# Tramdo.net
KiCad netlist of a schematic drawn in Altium Designer
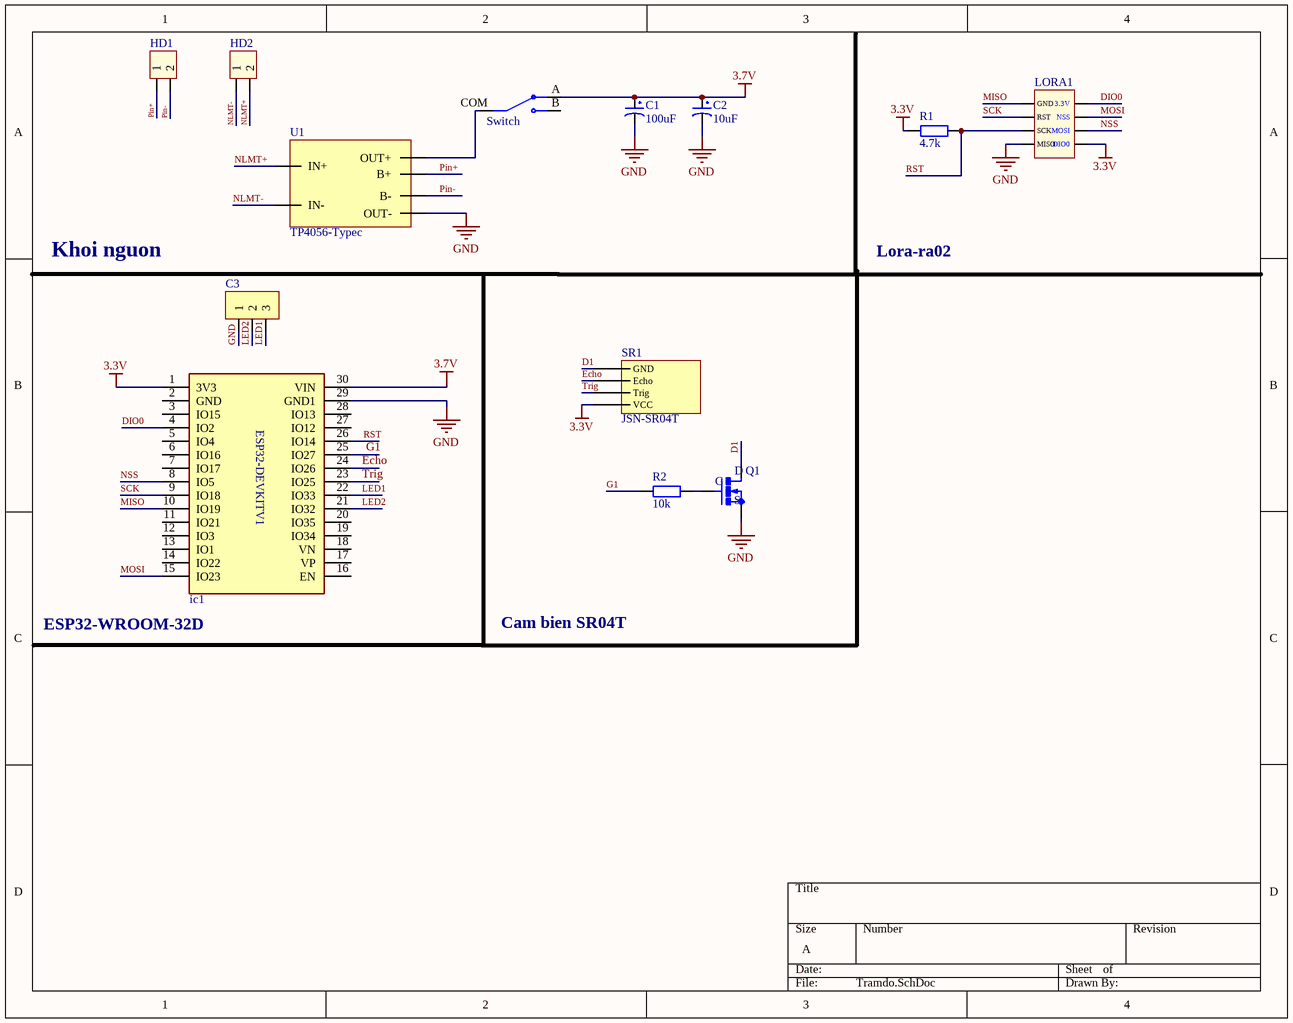
[diagram p0: Tramdo.SchDoc]

(export (version "E")
  (design (tool "Eeschema 10.0.6"))
  (components
    (comp (ref "C1")
      (value "100uF")
      (footprint "tu hoa 5mm")
      (description "Cắm")
      (libsource (lib "Altium_Lib_by_KhueNguyenCreator") (part "Tu Hoa 100uF 16V 5x11"))
    )
    (comp (ref "C2")
      (value "10uF")
      (footprint "tu hoa 4mm")
      (description "Cắm")
      (libsource (lib "Altium_Lib_by_KhueNguyenCreator") (part "Tu Hoa 10uF 16V 4x7"))
    )
    (comp (ref "C3")
      (value "JP3")
      (footprint "JP3-C1T")
      (description "WR-PHD 2.54 mm Angled Socket Header")
      (fields
        (field (name "MANUFACTURER") "Würth Elektronik eiSos GmbH")
        (field (name "PARTNO") "613003143121")
        (field (name "CREATED BY") "Karrer Zheng")
      )
      (libsource (lib "KhanhBK_Library_4") (part "JP3"))
    )
    (comp (ref "HD1")
      (value "Header 2")
      (footprint "HED2")
      (description "Header 2 (Green)")
      (libsource (lib "Integrated_Library1") (part "Hed2"))
    )
    (comp (ref "HD2")
      (value "Header 2")
      (footprint "HED2")
      (description "Header 2 (Green)")
      (libsource (lib "Integrated_Library1") (part "Hed2"))
    )
    (comp (ref "ic1")
      (value "ESP32 DevKit 30Pin")
      (footprint "ESP32 DevKit V1 30Pin CAo")
      (libsource (lib "Integrated_Library1") (part "ESP32 DevKit 30Pin"))
    )
    (comp (ref "LORA1")
      (value "Connector 4x2")
      (footprint "Lora-ra02")
      (libsource (lib "Thuvien_Tramdo") (part "LORA-Ra-02"))
    )
    (comp (ref "Q1")
      (value "2N7000")
      (footprint "TO92")
      (description "N-Channel 60 V 200mA (Ta) 400mW (Ta) Through Hole TO-92-3")
      (fields (field (name "MF") "onsemi"))
      (libsource (lib "Thuvien_Tramdo") (part "2N7000"))
    )
    (comp (ref "R1")
      (value "4.7k")
      (footprint "tro vach 1/4w")
      (description "Cắm")
      (libsource (lib "Altium_Lib_by_KhueNguyenCreator") (part "Tro Vach 1/4W 1% 4.7k"))
    )
    (comp (ref "R2")
      (value "10k")
      (footprint "tro vach 1/4w")
      (description "Cắm")
      (libsource (lib "Altium_Lib_by_KhueNguyenCreator") (part "Tro Vach 1/4W 1% 10k"))
    )
    (comp (ref "S1")
      (value "Switch")
      (footprint "SW_R1966ABLKBLKFR")
      (fields (field (name "MF") "E-Switch") (field (name "MP") "R1966ABLKBLKFR"))
      (libsource (lib "Integrated_Library1") (part "R1966ABLKBLKFR"))
    )
    (comp (ref "SR1")
      (value "JSN-SR04T")
      (footprint "JSN-SR04T")
      (description "Sensor sieu am")
      (libsource (lib "Thuvien_Tramdo") (part "JSN-SR04T"))
    )
    (comp (ref "U1")
      (value "TP4056-Typec")
      (footprint "TP4056")
      (libsource (lib "Thuvien_Tramdo") (part "TP4056-Typec"))
    )
  )
  (nets
    (net (code "1") (name "/D1") (class "Default")
      (node (ref "Q1") (pin "3") (pinfunction "D_3") (pintype "passive"))
      (node (ref "SR1") (pin "GND") (pinfunction "GND_GND") (pintype "passive"))
    )
    (net (code "2") (name "/DIO0") (class "Default")
      (node (ref "LORA1") (pin "5") (pinfunction "3.3V_5") (pintype "passive"))
      (node (ref "ic1") (pin "4") (pinfunction "IO2_4") (pintype "passive"))
    )
    (net (code "3") (name "/Echo") (class "Default")
      (node (ref "SR1") (pin "Echo") (pinfunction "Echo_Echo") (pintype "passive"))
      (node (ref "ic1") (pin "24") (pinfunction "IO26_24") (pintype "passive"))
    )
    (net (code "4") (name "/G1") (class "Default")
      (node (ref "R2") (pin "1") (pinfunction "1_1") (pintype "passive"))
      (node (ref "ic1") (pin "25") (pinfunction "IO27_25") (pintype "passive"))
    )
    (net (code "5") (name "/LED1") (class "Default")
      (node (ref "C3") (pin "3") (pinfunction "3_3") (pintype "passive"))
      (node (ref "ic1") (pin "22") (pinfunction "IO33_22") (pintype "passive"))
    )
    (net (code "6") (name "/LED2") (class "Default")
      (node (ref "C3") (pin "2") (pinfunction "2_2") (pintype "passive"))
      (node (ref "ic1") (pin "21") (pinfunction "IO32_21") (pintype "passive"))
    )
    (net (code "7") (name "/MISO") (class "Default")
      (node (ref "LORA1") (pin "1") (pinfunction "GND_1") (pintype "passive"))
      (node (ref "ic1") (pin "10") (pinfunction "IO19_10") (pintype "passive"))
    )
    (net (code "8") (name "/MOSI") (class "Default")
      (node (ref "LORA1") (pin "6") (pinfunction "NSS_6") (pintype "passive"))
      (node (ref "ic1") (pin "15") (pinfunction "IO23_15") (pintype "passive"))
    )
    (net (code "9") (name "/NLMT+") (class "Default")
      (node (ref "HD2") (pin "2") (pinfunction "2_2") (pintype "passive"))
      (node (ref "U1") (pin "IN+") (pinfunction "IN+_IN+") (pintype "power_in"))
    )
    (net (code "10") (name "/NLMT-") (class "Default")
      (node (ref "HD2") (pin "1") (pinfunction "1_1") (pintype "passive"))
      (node (ref "U1") (pin "IN-") (pinfunction "IN-_IN-") (pintype "passive"))
    )
    (net (code "11") (name "/NSS") (class "Default")
      (node (ref "LORA1") (pin "7") (pinfunction "MOSI_7") (pintype "passive"))
      (node (ref "ic1") (pin "8") (pinfunction "IO5_8") (pintype "passive"))
    )
    (net (code "12") (name "/Pin+") (class "Default")
      (node (ref "HD1") (pin "1") (pinfunction "1_1") (pintype "passive"))
      (node (ref "U1") (pin "B+") (pinfunction "B+_B+") (pintype "passive"))
    )
    (net (code "13") (name "/Pin-") (class "Default")
      (node (ref "HD1") (pin "2") (pinfunction "2_2") (pintype "passive"))
      (node (ref "U1") (pin "B-") (pinfunction "B-_B-") (pintype "passive"))
    )
    (net (code "14") (name "/RST") (class "Default")
      (node (ref "LORA1") (pin "3") (pinfunction "SCK_3") (pintype "passive"))
      (node (ref "R1") (pin "2") (pinfunction "2_2") (pintype "passive"))
      (node (ref "ic1") (pin "26") (pinfunction "IO14_26") (pintype "passive"))
    )
    (net (code "15") (name "/SCK") (class "Default")
      (node (ref "LORA1") (pin "2") (pinfunction "RST_2") (pintype "passive"))
      (node (ref "ic1") (pin "9") (pinfunction "IO18_9") (pintype "passive"))
    )
    (net (code "16") (name "/Trig") (class "Default")
      (node (ref "SR1") (pin "Trig") (pinfunction "Trig_Trig") (pintype "passive"))
      (node (ref "ic1") (pin "23") (pinfunction "IO25_23") (pintype "passive"))
    )
    (net (code "17") (name "3.3V") (class "Default")
      (node (ref "LORA1") (pin "8") (pinfunction "DIO0_8") (pintype "passive"))
      (node (ref "R1") (pin "1") (pinfunction "1_1") (pintype "passive"))
      (node (ref "SR1") (pin "VCC") (pinfunction "VCC_VCC") (pintype "passive"))
      (node (ref "ic1") (pin "1") (pinfunction "3V3_1") (pintype "passive"))
    )
    (net (code "18") (name "3.7V") (class "Default")
      (node (ref "C1") (pin "1") (pinfunction "1_1") (pintype "passive"))
      (node (ref "C2") (pin "1") (pinfunction "1_1") (pintype "passive"))
      (node (ref "S1") (pin "A") (pinfunction "6A_A") (pintype "passive"))
      (node (ref "ic1") (pin "30") (pinfunction "VIN_30") (pintype "passive"))
    )
    (net (code "19") (name "GND") (class "Default")
      (node (ref "C1") (pin "2") (pinfunction "2_2") (pintype "passive"))
      (node (ref "C2") (pin "2") (pinfunction "2_2") (pintype "passive"))
      (node (ref "C3") (pin "1") (pinfunction "1_1") (pintype "passive"))
      (node (ref "LORA1") (pin "4") (pinfunction "MISO_4") (pintype "passive"))
      (node (ref "Q1") (pin "1") (pinfunction "S_1") (pintype "passive"))
      (node (ref "U1") (pin "OUT-") (pinfunction "OUT-_OUT-") (pintype "passive"))
      (node (ref "ic1") (pin "29") (pinfunction "GND1_29") (pintype "passive"))
    )
    (net (code "20") (name "Net-(Q1-G)") (class "Default")
      (node (ref "Q1") (pin "2") (pinfunction "G_2") (pintype "passive"))
      (node (ref "R2") (pin "2") (pinfunction "2_2") (pintype "passive"))
    )
    (net (code "21") (name "Net-(S1-1)") (class "Default")
      (node (ref "S1") (pin "COM") (pinfunction "1_COM") (pintype "passive"))
      (node (ref "U1") (pin "OUT+") (pinfunction "OUT+_OUT+") (pintype "passive"))
    )
    (net (code "22") (name "unconnected-(S1-6A-PadB)") (class "Default")
      (node (ref "S1") (pin "B") (pinfunction "6A_B") (pintype "passive"))
    )
    (net (code "23") (name "unconnected-(ic1-EN-Pad16)") (class "Default")
      (node (ref "ic1") (pin "16") (pinfunction "EN_16") (pintype "passive"))
    )
    (net (code "24") (name "unconnected-(ic1-GND-Pad2)") (class "Default")
      (node (ref "ic1") (pin "2") (pinfunction "GND_2") (pintype "passive"))
    )
    (net (code "25") (name "unconnected-(ic1-IO1-Pad13)") (class "Default")
      (node (ref "ic1") (pin "13") (pinfunction "IO1_13") (pintype "passive"))
    )
    (net (code "26") (name "unconnected-(ic1-IO3-Pad12)") (class "Default")
      (node (ref "ic1") (pin "12") (pinfunction "IO3_12") (pintype "passive"))
    )
    (net (code "27") (name "unconnected-(ic1-IO4-Pad5)") (class "Default")
      (node (ref "ic1") (pin "5") (pinfunction "IO4_5") (pintype "passive"))
    )
    (net (code "28") (name "unconnected-(ic1-IO12-Pad27)") (class "Default")
      (node (ref "ic1") (pin "27") (pinfunction "IO12_27") (pintype "passive"))
    )
    (net (code "29") (name "unconnected-(ic1-IO13-Pad28)") (class "Default")
      (node (ref "ic1") (pin "28") (pinfunction "IO13_28") (pintype "passive"))
    )
    (net (code "30") (name "unconnected-(ic1-IO15-Pad3)") (class "Default")
      (node (ref "ic1") (pin "3") (pinfunction "IO15_3") (pintype "passive"))
    )
    (net (code "31") (name "unconnected-(ic1-IO16-Pad6)") (class "Default")
      (node (ref "ic1") (pin "6") (pinfunction "IO16_6") (pintype "passive"))
    )
    (net (code "32") (name "unconnected-(ic1-IO17-Pad7)") (class "Default")
      (node (ref "ic1") (pin "7") (pinfunction "IO17_7") (pintype "passive"))
    )
    (net (code "33") (name "unconnected-(ic1-IO21-Pad11)") (class "Default")
      (node (ref "ic1") (pin "11") (pinfunction "IO21_11") (pintype "passive"))
    )
    (net (code "34") (name "unconnected-(ic1-IO22-Pad14)") (class "Default")
      (node (ref "ic1") (pin "14") (pinfunction "IO22_14") (pintype "passive"))
    )
    (net (code "35") (name "unconnected-(ic1-IO34-Pad19)") (class "Default")
      (node (ref "ic1") (pin "19") (pinfunction "IO34_19") (pintype "passive"))
    )
    (net (code "36") (name "unconnected-(ic1-IO35-Pad20)") (class "Default")
      (node (ref "ic1") (pin "20") (pinfunction "IO35_20") (pintype "passive"))
    )
    (net (code "37") (name "unconnected-(ic1-VN-Pad18)") (class "Default")
      (node (ref "ic1") (pin "18") (pinfunction "VN_18") (pintype "passive"))
    )
    (net (code "38") (name "unconnected-(ic1-VP-Pad17)") (class "Default")
      (node (ref "ic1") (pin "17") (pinfunction "VP_17") (pintype "passive"))
    )
  )
)
